# 2021-06-29_LN2_Autofill_Controller.net
KiCad netlist of a schematic drawn in EAGLE
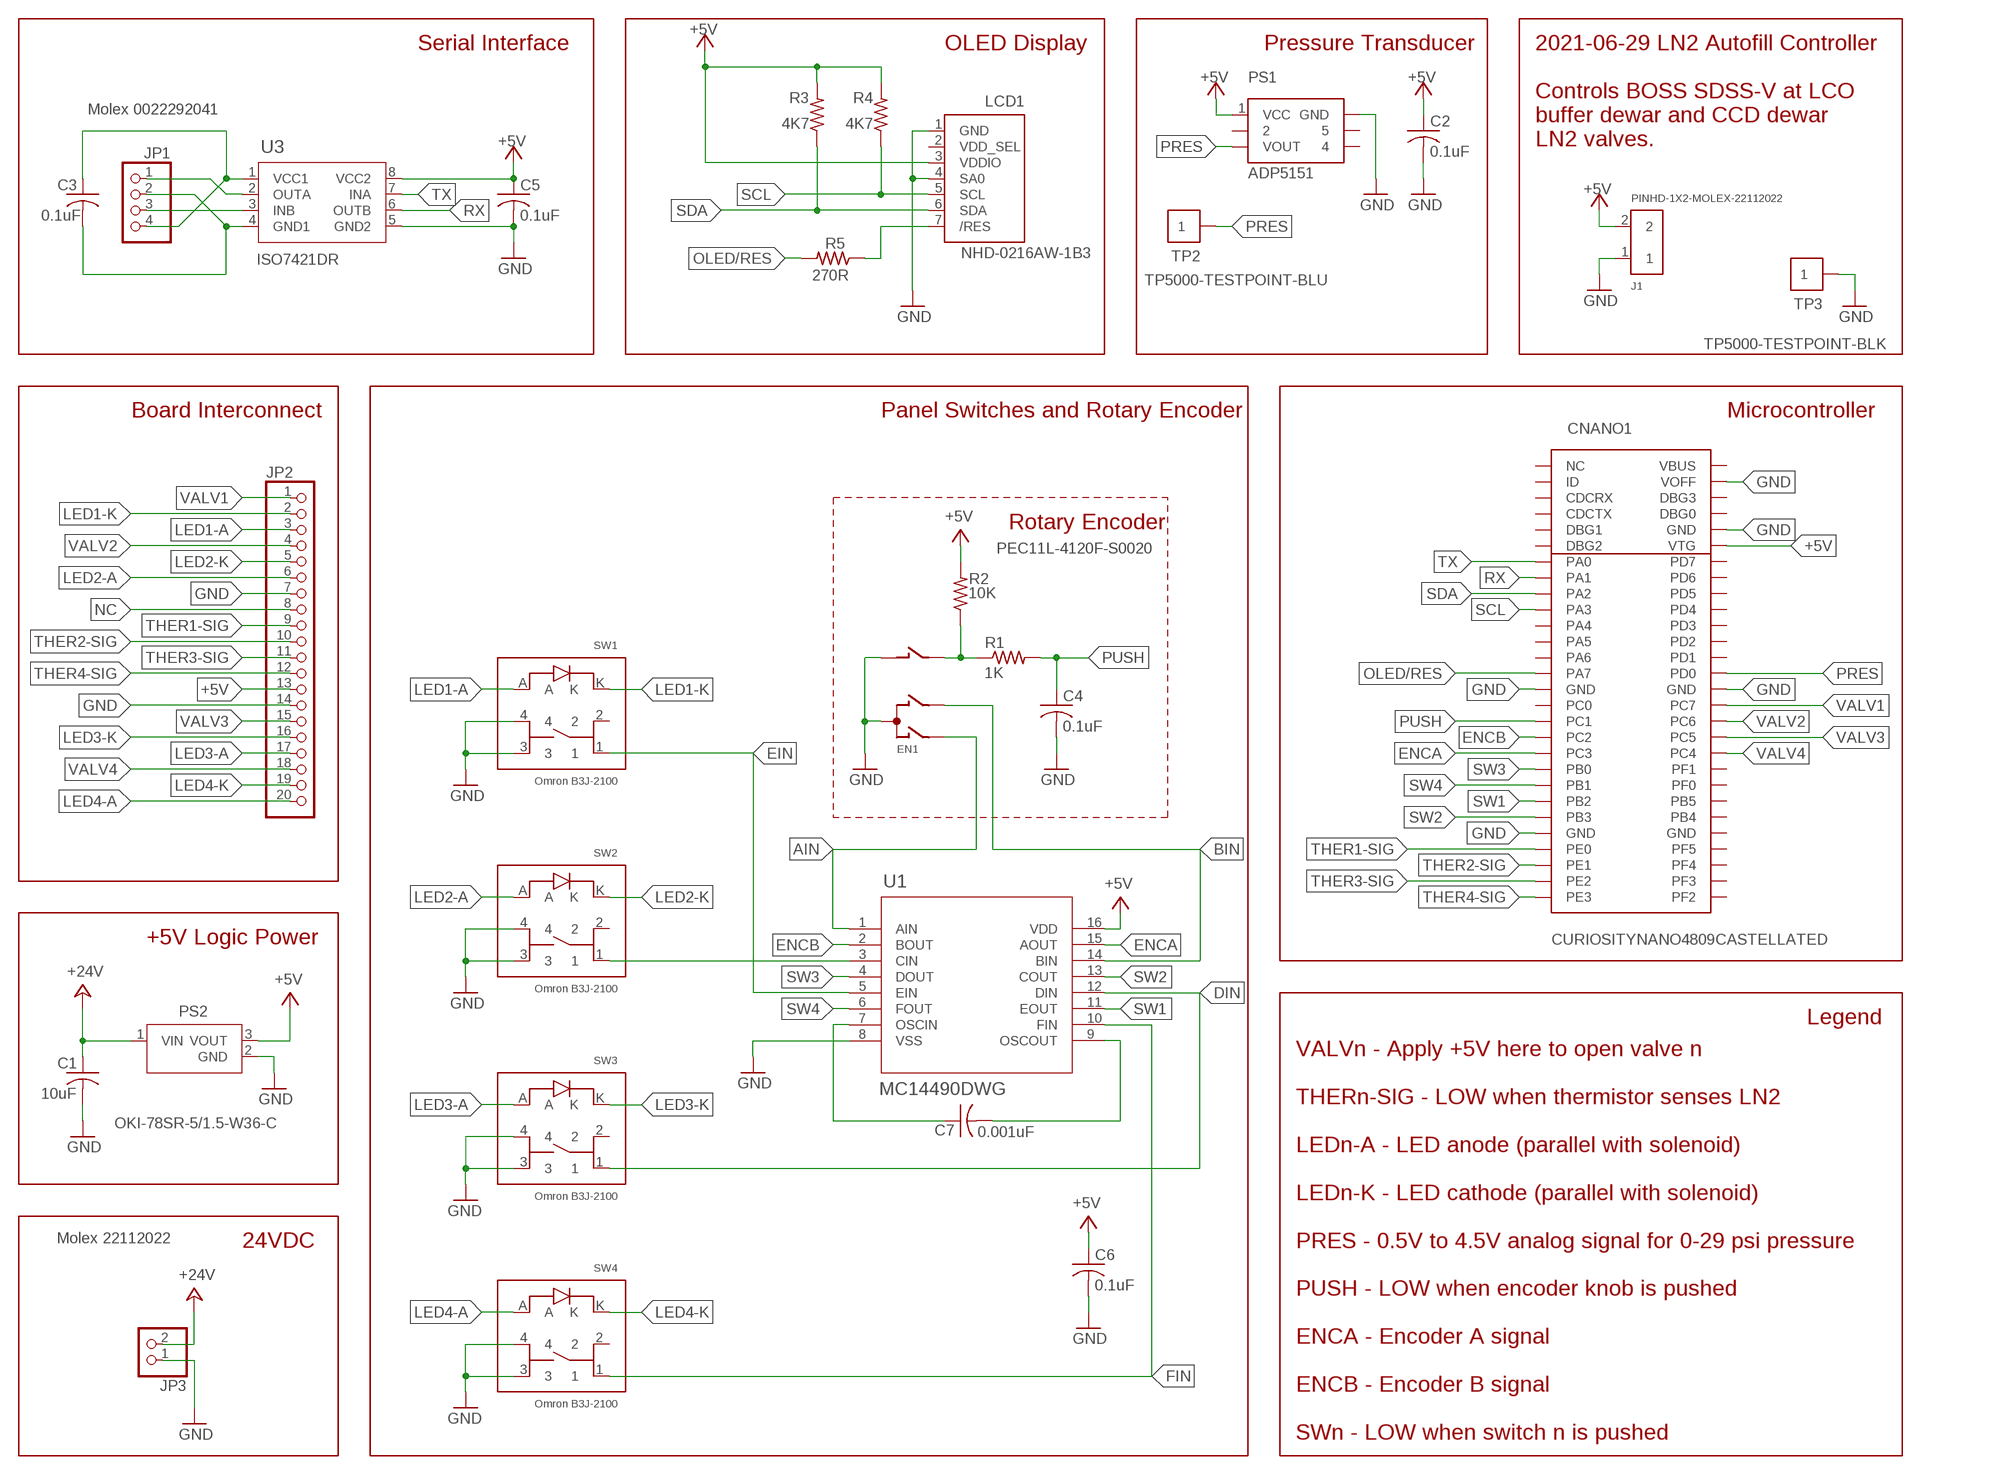
[diagram p0: schematic, sheet 1]

(export (version "E")
  (design (tool "Eeschema 10.0.6"))
  (components
    (comp (ref "C1")
      (value "10uF")
      (footprint "eagle-import:C1210K")
      (libsource (lib "eagle-import") (part "C-USC1210K"))
    )
    (comp (ref "C2")
      (value "0.1uF")
      (footprint "eagle-import:C0805")
      (libsource (lib "eagle-import") (part "C-USC0805"))
    )
    (comp (ref "C3")
      (value "0.1uF")
      (footprint "eagle-import:C0805")
      (libsource (lib "eagle-import") (part "C-USC0805"))
    )
    (comp (ref "C4")
      (value "0.1uF")
      (footprint "eagle-import:C0805")
      (libsource (lib "eagle-import") (part "C-USC0805"))
    )
    (comp (ref "C5")
      (value "0.1uF")
      (footprint "eagle-import:C0805")
      (libsource (lib "eagle-import") (part "C-USC0805"))
    )
    (comp (ref "C6")
      (value "0.1uF")
      (footprint "eagle-import:C0805")
      (libsource (lib "eagle-import") (part "C-USC0805"))
    )
    (comp (ref "C7")
      (value "0.001uF")
      (footprint "eagle-import:C0805")
      (libsource (lib "eagle-import") (part "C-USC0805"))
    )
    (comp (ref "CNANO1")
      (value "CURIOSITYNANO4809CASTELLATED")
      (footprint "eagle-import:CURIOSITYNANO4809CASTELLATED")
      (libsource (lib "eagle-import") (part "CURIOSITYNANO4809CASTELLATED"))
    )
    (comp (ref "EN1")
      (value "PEC11L-4120F-S0020")
      (footprint "eagle-import:ENC-BOURNES-PEC11L")
      (libsource (lib "eagle-import") (part "ENC-BOURNES-PEC11L"))
    )
    (comp (ref "J1")
      (value "PINHD-1X2-MOLEX-22112022")
      (footprint "eagle-import:1X02-MOLEX-22112022")
      (libsource (lib "eagle-import") (part "PINHD-1X2-MOLEX-22112022"))
    )
    (comp (ref "JP1")
      (value "Molex 0022292041")
      (footprint "eagle-import:MOLEX-04-VERT")
      (libsource (lib "eagle-import") (part "PINHD-1X4MOLEX-04-VERT"))
    )
    (comp (ref "JP2")
      (value "PINHD-1X20")
      (footprint "eagle-import:1X20")
      (libsource (lib "eagle-import") (part "PINHD-1X20"))
    )
    (comp (ref "JP3")
      (value "Molex 22112022")
      (footprint "eagle-import:MOLEX-02-VERT")
      (libsource (lib "eagle-import") (part "PINHD-1X2MOLEX-02-VERT"))
    )
    (comp (ref "LCD1")
      (value "NHD-0216AW-1B3")
      (footprint "eagle-import:LCD-NEWHAVEN-16X2")
      (libsource (lib "eagle-import") (part "LCD-NEWHAVEN-16X2"))
    )
    (comp (ref "PS1")
      (value "ADP5151")
      (footprint "eagle-import:PRESSURE-SENSOR-ADP5151")
      (libsource (lib "eagle-import") (part "PRESSURE-SENSOR-ADP5151"))
    )
    (comp (ref "PS2")
      (value "OKI-78SR-5/1.5-W36-C")
      (footprint "eagle-import:CONV_OKI-78SR-5_1.5-W36-C")
      (fields
        (field (name "DIGI-KEY_PART_NUMBER") "811-2196-5-ND")
        (field (name "MF") "Murata Power Solutions Inc.")
      )
      (libsource (lib "eagle-import") (part "OKI-78SR-5/1.5-W36-C"))
    )
    (comp (ref "R1")
      (value "1K")
      (footprint "eagle-import:R0805")
      (libsource (lib "eagle-import") (part "R-US_R0805"))
    )
    (comp (ref "R2")
      (value "10K")
      (footprint "eagle-import:R0805")
      (libsource (lib "eagle-import") (part "R-US_R0805"))
    )
    (comp (ref "R3")
      (value "4K7")
      (footprint "eagle-import:R0805")
      (libsource (lib "eagle-import") (part "R-US_R0805"))
    )
    (comp (ref "R4")
      (value "4K7")
      (footprint "eagle-import:R0805")
      (libsource (lib "eagle-import") (part "R-US_R0805"))
    )
    (comp (ref "R5")
      (value "270R")
      (footprint "eagle-import:R0805")
      (libsource (lib "eagle-import") (part "R-US_R0805"))
    )
    (comp (ref "SW1")
      (value "Omron B3J-2100")
      (footprint "eagle-import:SWITCH-OMRON-B3J-1LED")
      (libsource (lib "eagle-import") (part "SWITCH-OMRON-B3J-1LED"))
    )
    (comp (ref "SW2")
      (value "Omron B3J-2100")
      (footprint "eagle-import:SWITCH-OMRON-B3J-1LED")
      (libsource (lib "eagle-import") (part "SWITCH-OMRON-B3J-1LED"))
    )
    (comp (ref "SW3")
      (value "Omron B3J-2100")
      (footprint "eagle-import:SWITCH-OMRON-B3J-1LED")
      (libsource (lib "eagle-import") (part "SWITCH-OMRON-B3J-1LED"))
    )
    (comp (ref "SW4")
      (value "Omron B3J-2100")
      (footprint "eagle-import:SWITCH-OMRON-B3J-1LED")
      (libsource (lib "eagle-import") (part "SWITCH-OMRON-B3J-1LED"))
    )
    (comp (ref "TP2")
      (value "TP5000-TESTPOINT-BLU")
      (footprint "eagle-import:TP5000-TESTPOINT-BLU")
      (libsource (lib "eagle-import") (part "TP5000-TESTPOINT-BLU"))
    )
    (comp (ref "TP3")
      (value "TP5000-TESTPOINT-BLK")
      (footprint "eagle-import:TP5000-TESTPOINT-BLK")
      (libsource (lib "eagle-import") (part "TP5000-TESTPOINT-BLK"))
    )
    (comp (ref "U1")
      (value "MC14490DWG")
      (footprint "eagle-import:SOIC127P1030X265-16N")
      (libsource (lib "eagle-import") (part "DEBOUNCER-MC14490DWGSOIC-16-WB"))
    )
    (comp (ref "U3")
      (value "ISO7421DR")
      (footprint "eagle-import:SOIC127P599X175-8N")
      (libsource (lib "eagle-import") (part "ISO7421DRTI-SOIC-D8"))
    )
  )
  (nets
    (net (code "1") (name "+5V") (class "Default")
      (node (ref "C2") (pin "1") (pinfunction "1_1") (pintype "passive"))
      (node (ref "C5") (pin "1") (pinfunction "1_1") (pintype "passive"))
      (node (ref "C6") (pin "1") (pinfunction "1_1") (pintype "passive"))
      (node (ref "CNANO1") (pin "VTG") (pinfunction "VTG_VTG") (pintype "bidirectional"))
      (node (ref "J1") (pin "2") (pinfunction "2_2") (pintype "bidirectional"))
      (node (ref "JP2") (pin "13") (pinfunction "13_13") (pintype "passive"))
      (node (ref "LCD1") (pin "3") (pinfunction "VDDIO_3") (pintype "bidirectional"))
      (node (ref "PS1") (pin "1") (pinfunction "VCC_1") (pintype "bidirectional"))
      (node (ref "PS2") (pin "3") (pinfunction "VOUT_3") (pintype "power_in"))
      (node (ref "R2") (pin "2") (pinfunction "2_2") (pintype "passive"))
      (node (ref "R3") (pin "2") (pinfunction "2_2") (pintype "passive"))
      (node (ref "R4") (pin "2") (pinfunction "2_2") (pintype "passive"))
      (node (ref "U1") (pin "16") (pinfunction "VDD_16") (pintype "power_in"))
      (node (ref "U3") (pin "8") (pinfunction "VCC2_8") (pintype "power_in"))
    )
    (net (code "2") (name "+24V") (class "Default")
      (node (ref "C1") (pin "1") (pinfunction "1_1") (pintype "passive"))
      (node (ref "JP3") (pin "2") (pinfunction "2_2") (pintype "passive"))
      (node (ref "PS2") (pin "1") (pinfunction "VIN_1") (pintype "input"))
    )
    (net (code "3") (name "AIN") (class "Default")
      (node (ref "EN1") (pin "A") (pinfunction "A_A") (pintype "passive"))
      (node (ref "U1") (pin "1") (pinfunction "AIN_1") (pintype "input"))
    )
    (net (code "4") (name "BIN") (class "Default")
      (node (ref "EN1") (pin "B") (pinfunction "B_B") (pintype "passive"))
      (node (ref "U1") (pin "14") (pinfunction "BIN_14") (pintype "input"))
    )
    (net (code "5") (name "DIN") (class "Default")
      (node (ref "SW3") (pin "1") (pinfunction "1_1") (pintype "bidirectional"))
      (node (ref "U1") (pin "12") (pinfunction "DIN_12") (pintype "input"))
    )
    (net (code "6") (name "EIN") (class "Default")
      (node (ref "SW1") (pin "1") (pinfunction "1_1") (pintype "bidirectional"))
      (node (ref "U1") (pin "5") (pinfunction "EIN_5") (pintype "input"))
    )
    (net (code "7") (name "ENCA") (class "Default")
      (node (ref "CNANO1") (pin "PC3") (pinfunction "PC3_PC3") (pintype "bidirectional"))
      (node (ref "U1") (pin "15") (pinfunction "AOUT_15") (pintype "output"))
    )
    (net (code "8") (name "ENCB") (class "Default")
      (node (ref "CNANO1") (pin "PC2") (pinfunction "PC2_PC2") (pintype "bidirectional"))
      (node (ref "U1") (pin "2") (pinfunction "BOUT_2") (pintype "output"))
    )
    (net (code "9") (name "FIN") (class "Default")
      (node (ref "SW4") (pin "1") (pinfunction "1_1") (pintype "bidirectional"))
      (node (ref "U1") (pin "10") (pinfunction "FIN_10") (pintype "input"))
    )
    (net (code "10") (name "GND") (class "Default")
      (node (ref "C1") (pin "2") (pinfunction "2_2") (pintype "passive"))
      (node (ref "C2") (pin "2") (pinfunction "2_2") (pintype "passive"))
      (node (ref "C4") (pin "2") (pinfunction "2_2") (pintype "passive"))
      (node (ref "C5") (pin "2") (pinfunction "2_2") (pintype "passive"))
      (node (ref "C6") (pin "2") (pinfunction "2_2") (pintype "passive"))
      (node (ref "CNANO1") (pin "GND15") (pinfunction "GND_GND15") (pintype "bidirectional"))
      (node (ref "CNANO1") (pin "GND24") (pinfunction "GND_GND24") (pintype "bidirectional"))
      (node (ref "CNANO1") (pin "GND42") (pinfunction "GND_GND42") (pintype "bidirectional"))
      (node (ref "CNANO1") (pin "GND52") (pinfunction "GND_GND52") (pintype "bidirectional"))
      (node (ref "CNANO1") (pin "VOFF") (pinfunction "VOFF_VOFF") (pintype "bidirectional"))
      (node (ref "EN1") (pin "2") (pinfunction "C1_2") (pintype "passive"))
      (node (ref "EN1") (pin "C") (pinfunction "C_C") (pintype "passive"))
      (node (ref "J1") (pin "1") (pinfunction "1_1") (pintype "bidirectional"))
      (node (ref "JP2") (pin "14") (pinfunction "14_14") (pintype "passive"))
      (node (ref "JP2") (pin "7") (pinfunction "7_7") (pintype "passive"))
      (node (ref "JP3") (pin "1") (pinfunction "1_1") (pintype "passive"))
      (node (ref "LCD1") (pin "1") (pinfunction "GND_1") (pintype "bidirectional"))
      (node (ref "LCD1") (pin "4") (pinfunction "SA0_4") (pintype "bidirectional"))
      (node (ref "PS1") (pin "6") (pinfunction "GND_6") (pintype "bidirectional"))
      (node (ref "PS2") (pin "2") (pinfunction "GND_2") (pintype "power_in"))
      (node (ref "SW1") (pin "3") (pinfunction "3_3") (pintype "bidirectional"))
      (node (ref "SW1") (pin "4") (pinfunction "4_4") (pintype "bidirectional"))
      (node (ref "SW2") (pin "3") (pinfunction "3_3") (pintype "bidirectional"))
      (node (ref "SW2") (pin "4") (pinfunction "4_4") (pintype "bidirectional"))
      (node (ref "SW3") (pin "3") (pinfunction "3_3") (pintype "bidirectional"))
      (node (ref "SW3") (pin "4") (pinfunction "4_4") (pintype "bidirectional"))
      (node (ref "SW4") (pin "3") (pinfunction "3_3") (pintype "bidirectional"))
      (node (ref "SW4") (pin "4") (pinfunction "4_4") (pintype "bidirectional"))
      (node (ref "TP3") (pin "P$1") (pinfunction "1_P$1") (pintype "bidirectional"))
      (node (ref "U1") (pin "8") (pinfunction "VSS_8") (pintype "power_in"))
      (node (ref "U3") (pin "5") (pinfunction "GND2_5") (pintype "power_in"))
    )
    (net (code "11") (name "LED1-A") (class "Default")
      (node (ref "JP2") (pin "3") (pinfunction "3_3") (pintype "passive"))
      (node (ref "SW1") (pin "A") (pinfunction "A_A") (pintype "bidirectional"))
    )
    (net (code "12") (name "LED1-K") (class "Default")
      (node (ref "JP2") (pin "2") (pinfunction "2_2") (pintype "passive"))
      (node (ref "SW1") (pin "K") (pinfunction "K_K") (pintype "bidirectional"))
    )
    (net (code "13") (name "LED2-A") (class "Default")
      (node (ref "JP2") (pin "6") (pinfunction "6_6") (pintype "passive"))
      (node (ref "SW2") (pin "A") (pinfunction "A_A") (pintype "bidirectional"))
    )
    (net (code "14") (name "LED2-K") (class "Default")
      (node (ref "JP2") (pin "5") (pinfunction "5_5") (pintype "passive"))
      (node (ref "SW2") (pin "K") (pinfunction "K_K") (pintype "bidirectional"))
    )
    (net (code "15") (name "LED3-A") (class "Default")
      (node (ref "JP2") (pin "17") (pinfunction "17_17") (pintype "passive"))
      (node (ref "SW3") (pin "A") (pinfunction "A_A") (pintype "bidirectional"))
    )
    (net (code "16") (name "LED3-K") (class "Default")
      (node (ref "JP2") (pin "16") (pinfunction "16_16") (pintype "passive"))
      (node (ref "SW3") (pin "K") (pinfunction "K_K") (pintype "bidirectional"))
    )
    (net (code "17") (name "LED4-A") (class "Default")
      (node (ref "JP2") (pin "20") (pinfunction "20_20") (pintype "passive"))
      (node (ref "SW4") (pin "A") (pinfunction "A_A") (pintype "bidirectional"))
    )
    (net (code "18") (name "LED4-K") (class "Default")
      (node (ref "JP2") (pin "19") (pinfunction "19_19") (pintype "passive"))
      (node (ref "SW4") (pin "K") (pinfunction "K_K") (pintype "bidirectional"))
    )
    (net (code "19") (name "NC") (class "Default")
      (node (ref "JP2") (pin "8") (pinfunction "8_8") (pintype "passive"))
    )
    (net (code "20") (name "Net-(EN1-B1)") (class "Default")
      (node (ref "EN1") (pin "1") (pinfunction "B1_1") (pintype "passive"))
      (node (ref "R1") (pin "1") (pinfunction "1_1") (pintype "passive"))
      (node (ref "R2") (pin "1") (pinfunction "1_1") (pintype "passive"))
    )
    (net (code "21") (name "Net-(LCD1-{slash}RES)") (class "Default")
      (node (ref "LCD1") (pin "7") (pinfunction "/RES_7") (pintype "bidirectional"))
      (node (ref "R5") (pin "1") (pinfunction "1_1") (pintype "passive"))
    )
    (net (code "22") (name "Net-(U1-CIN)") (class "Default")
      (node (ref "SW2") (pin "1") (pinfunction "1_1") (pintype "bidirectional"))
      (node (ref "U1") (pin "3") (pinfunction "CIN_3") (pintype "input"))
    )
    (net (code "23") (name "Net-(U1-OSCIN)") (class "Default")
      (node (ref "C7") (pin "1") (pinfunction "1_1") (pintype "passive"))
      (node (ref "U1") (pin "7") (pinfunction "OSCIN_7") (pintype "input"))
    )
    (net (code "24") (name "Net-(U1-OSCOUT)") (class "Default")
      (node (ref "C7") (pin "2") (pinfunction "2_2") (pintype "passive"))
      (node (ref "U1") (pin "9") (pinfunction "OSCOUT_9") (pintype "output"))
    )
    (net (code "25") (name "Net-(U3-GND1)") (class "Default")
      (node (ref "C3") (pin "2") (pinfunction "2_2") (pintype "passive"))
      (node (ref "JP1") (pin "2") (pinfunction "2_2") (pintype "passive"))
      (node (ref "U3") (pin "4") (pinfunction "GND1_4") (pintype "power_in"))
    )
    (net (code "26") (name "Net-(U3-INB)") (class "Default")
      (node (ref "JP1") (pin "3") (pinfunction "3_3") (pintype "passive"))
      (node (ref "U3") (pin "3") (pinfunction "INB_3") (pintype "input"))
    )
    (net (code "27") (name "Net-(U3-OUTA)") (class "Default")
      (node (ref "JP1") (pin "1") (pinfunction "1_1") (pintype "passive"))
      (node (ref "U3") (pin "2") (pinfunction "OUTA_2") (pintype "output"))
    )
    (net (code "28") (name "Net-(U3-VCC1)") (class "Default")
      (node (ref "C3") (pin "1") (pinfunction "1_1") (pintype "passive"))
      (node (ref "JP1") (pin "4") (pinfunction "4_4") (pintype "passive"))
      (node (ref "U3") (pin "1") (pinfunction "VCC1_1") (pintype "power_in"))
    )
    (net (code "29") (name "OLED{slash}RES") (class "Default")
      (node (ref "CNANO1") (pin "PA7-SS") (pinfunction "PA7_PA7-SS") (pintype "bidirectional"))
      (node (ref "R5") (pin "2") (pinfunction "2_2") (pintype "passive"))
    )
    (net (code "30") (name "PRES") (class "Default")
      (node (ref "CNANO1") (pin "PD0-AIN0") (pinfunction "PD0_PD0-AIN0") (pintype "bidirectional"))
      (node (ref "PS1") (pin "3") (pinfunction "VOUT_3") (pintype "bidirectional"))
      (node (ref "TP2") (pin "P$1") (pinfunction "1_P$1") (pintype "bidirectional"))
    )
    (net (code "31") (name "PUSH") (class "Default")
      (node (ref "C4") (pin "1") (pinfunction "1_1") (pintype "passive"))
      (node (ref "CNANO1") (pin "PC1-RX") (pinfunction "PC1_PC1-RX") (pintype "bidirectional"))
      (node (ref "R1") (pin "2") (pinfunction "2_2") (pintype "passive"))
    )
    (net (code "32") (name "RX") (class "Default")
      (node (ref "CNANO1") (pin "PA1-RX") (pinfunction "PA1_PA1-RX") (pintype "bidirectional"))
      (node (ref "U3") (pin "6") (pinfunction "OUTB_6") (pintype "output"))
    )
    (net (code "33") (name "SCL") (class "Default")
      (node (ref "CNANO1") (pin "PA3-SCL") (pinfunction "PA3_PA3-SCL") (pintype "bidirectional"))
      (node (ref "LCD1") (pin "5") (pinfunction "SCL_5") (pintype "bidirectional"))
      (node (ref "R4") (pin "1") (pinfunction "1_1") (pintype "passive"))
    )
    (net (code "34") (name "SDA") (class "Default")
      (node (ref "CNANO1") (pin "PA2-SDA") (pinfunction "PA2_PA2-SDA") (pintype "bidirectional"))
      (node (ref "LCD1") (pin "6") (pinfunction "SDA_6") (pintype "bidirectional"))
      (node (ref "R3") (pin "1") (pinfunction "1_1") (pintype "passive"))
    )
    (net (code "35") (name "SW1") (class "Default")
      (node (ref "CNANO1") (pin "PB2") (pinfunction "PB2_PB2") (pintype "bidirectional"))
      (node (ref "U1") (pin "11") (pinfunction "EOUT_11") (pintype "output"))
    )
    (net (code "36") (name "SW2") (class "Default")
      (node (ref "CNANO1") (pin "PB3") (pinfunction "PB3_PB3") (pintype "bidirectional"))
      (node (ref "U1") (pin "13") (pinfunction "COUT_13") (pintype "output"))
    )
    (net (code "37") (name "SW3") (class "Default")
      (node (ref "CNANO1") (pin "PB0-TX") (pinfunction "PB0_PB0-TX") (pintype "bidirectional"))
      (node (ref "U1") (pin "4") (pinfunction "DOUT_4") (pintype "output"))
    )
    (net (code "38") (name "SW4") (class "Default")
      (node (ref "CNANO1") (pin "PB1-RX") (pinfunction "PB1_PB1-RX") (pintype "bidirectional"))
      (node (ref "U1") (pin "6") (pinfunction "FOUT_6") (pintype "output"))
    )
    (net (code "39") (name "THER1-SIG") (class "Default")
      (node (ref "CNANO1") (pin "PE0") (pinfunction "PE0_PE0") (pintype "bidirectional"))
      (node (ref "JP2") (pin "9") (pinfunction "9_9") (pintype "passive"))
    )
    (net (code "40") (name "THER2-SIG") (class "Default")
      (node (ref "CNANO1") (pin "PE1") (pinfunction "PE1_PE1") (pintype "bidirectional"))
      (node (ref "JP2") (pin "10") (pinfunction "10_10") (pintype "passive"))
    )
    (net (code "41") (name "THER3-SIG") (class "Default")
      (node (ref "CNANO1") (pin "PE2") (pinfunction "PE2_PE2") (pintype "bidirectional"))
      (node (ref "JP2") (pin "11") (pinfunction "11_11") (pintype "passive"))
    )
    (net (code "42") (name "THER4-SIG") (class "Default")
      (node (ref "CNANO1") (pin "PE3") (pinfunction "PE3_PE3") (pintype "bidirectional"))
      (node (ref "JP2") (pin "12") (pinfunction "12_12") (pintype "passive"))
    )
    (net (code "43") (name "TX") (class "Default")
      (node (ref "CNANO1") (pin "PA0-TX") (pinfunction "PA0_PA0-TX") (pintype "bidirectional"))
      (node (ref "U3") (pin "7") (pinfunction "INA_7") (pintype "input"))
    )
    (net (code "44") (name "VALV1") (class "Default")
      (node (ref "CNANO1") (pin "PC7") (pinfunction "PC7_PC7") (pintype "bidirectional"))
      (node (ref "JP2") (pin "1") (pinfunction "1_1") (pintype "passive"))
    )
    (net (code "45") (name "VALV2") (class "Default")
      (node (ref "CNANO1") (pin "PC6") (pinfunction "PC6_PC6") (pintype "bidirectional"))
      (node (ref "JP2") (pin "4") (pinfunction "4_4") (pintype "passive"))
    )
    (net (code "46") (name "VALV3") (class "Default")
      (node (ref "CNANO1") (pin "PC5") (pinfunction "PC5_PC5") (pintype "bidirectional"))
      (node (ref "JP2") (pin "15") (pinfunction "15_15") (pintype "passive"))
    )
    (net (code "47") (name "VALV4") (class "Default")
      (node (ref "CNANO1") (pin "PC4") (pinfunction "PC4_PC4") (pintype "bidirectional"))
      (node (ref "JP2") (pin "18") (pinfunction "18_18") (pintype "passive"))
    )
    (net (code "48") (name "unconnected-(CNANO1-CDCRX-PadPB0-RX)") (class "Default")
      (node (ref "CNANO1") (pin "PB0-RX") (pinfunction "CDCRX_PB0-RX") (pintype "bidirectional"))
    )
    (net (code "49") (name "unconnected-(CNANO1-CDCTX-PadPB1-TX)") (class "Default")
      (node (ref "CNANO1") (pin "PB1-TX") (pinfunction "CDCTX_PB1-TX") (pintype "bidirectional"))
    )
    (net (code "50") (name "unconnected-(CNANO1-DBG0-PadUPDI)") (class "Default")
      (node (ref "CNANO1") (pin "UPDI") (pinfunction "DBG0_UPDI") (pintype "bidirectional"))
    )
    (net (code "51") (name "unconnected-(CNANO1-DBG1-PadPF3-5)") (class "Default")
      (node (ref "CNANO1") (pin "PF3-5") (pinfunction "DBG1_PF3-5") (pintype "bidirectional"))
    )
    (net (code "52") (name "unconnected-(CNANO1-DBG2-PadPF2-6)") (class "Default")
      (node (ref "CNANO1") (pin "PF2-6") (pinfunction "DBG2_PF2-6") (pintype "bidirectional"))
    )
    (net (code "53") (name "unconnected-(CNANO1-DBG3-PadPF6-SW0)") (class "Default")
      (node (ref "CNANO1") (pin "PF6-SW0") (pinfunction "DBG3_PF6-SW0") (pintype "bidirectional"))
    )
    (net (code "54") (name "unconnected-(CNANO1-GND-PadGND33)") (class "Default")
      (node (ref "CNANO1") (pin "GND33") (pinfunction "GND_GND33") (pintype "bidirectional"))
    )
    (net (code "55") (name "unconnected-(CNANO1-PA4-PadPA4-MOSI)") (class "Default")
      (node (ref "CNANO1") (pin "PA4-MOSI") (pinfunction "PA4_PA4-MOSI") (pintype "bidirectional"))
    )
    (net (code "56") (name "unconnected-(CNANO1-PA5-PadPA5-MISO)") (class "Default")
      (node (ref "CNANO1") (pin "PA5-MISO") (pinfunction "PA5_PA5-MISO") (pintype "bidirectional"))
    )
    (net (code "57") (name "unconnected-(CNANO1-PA6-PadPA6-SCK)") (class "Default")
      (node (ref "CNANO1") (pin "PA6-SCK") (pinfunction "PA6_PA6-SCK") (pintype "bidirectional"))
    )
    (net (code "58") (name "unconnected-(CNANO1-PC0-PadPC0-TX)") (class "Default")
      (node (ref "CNANO1") (pin "PC0-TX") (pinfunction "PC0_PC0-TX") (pintype "bidirectional"))
    )
    (net (code "59") (name "unconnected-(CNANO1-PD1-PadPD1-AIN1)") (class "Default")
      (node (ref "CNANO1") (pin "PD1-AIN1") (pinfunction "PD1_PD1-AIN1") (pintype "bidirectional"))
    )
    (net (code "60") (name "unconnected-(CNANO1-PD2-PadPD2-AIN2)") (class "Default")
      (node (ref "CNANO1") (pin "PD2-AIN2") (pinfunction "PD2_PD2-AIN2") (pintype "bidirectional"))
    )
    (net (code "61") (name "unconnected-(CNANO1-PD3-PadPD3-AIN3)") (class "Default")
      (node (ref "CNANO1") (pin "PD3-AIN3") (pinfunction "PD3_PD3-AIN3") (pintype "bidirectional"))
    )
    (net (code "62") (name "unconnected-(CNANO1-PD4-PadPD4-AIN4)") (class "Default")
      (node (ref "CNANO1") (pin "PD4-AIN4") (pinfunction "PD4_PD4-AIN4") (pintype "bidirectional"))
    )
    (net (code "63") (name "unconnected-(CNANO1-PD5-PadPD5-AIN5)") (class "Default")
      (node (ref "CNANO1") (pin "PD5-AIN5") (pinfunction "PD5_PD5-AIN5") (pintype "bidirectional"))
    )
    (net (code "64") (name "unconnected-(CNANO1-PD6-PadPD6-AIN6)") (class "Default")
      (node (ref "CNANO1") (pin "PD6-AIN6") (pinfunction "PD6_PD6-AIN6") (pintype "bidirectional"))
    )
    (net (code "65") (name "unconnected-(CNANO1-PD7-PadPD7-AIN7)") (class "Default")
      (node (ref "CNANO1") (pin "PD7-AIN7") (pinfunction "PD7_PD7-AIN7") (pintype "bidirectional"))
    )
    (net (code "66") (name "unconnected-(CNANO1-PF0-PadPF0-TOSC1)") (class "Default")
      (node (ref "CNANO1") (pin "PF0-TOSC1") (pinfunction "PF0_PF0-TOSC1") (pintype "bidirectional"))
    )
    (net (code "67") (name "unconnected-(CNANO1-PF1-PadPF1-TOSC2)") (class "Default")
      (node (ref "CNANO1") (pin "PF1-TOSC2") (pinfunction "PF1_PF1-TOSC2") (pintype "bidirectional"))
    )
    (net (code "68") (name "unconnected-(CNANO1-PF5-PadPF5-LED)") (class "Default")
      (node (ref "CNANO1") (pin "PF5-LED") (pinfunction "PF5_PF5-LED") (pintype "bidirectional"))
    )
    (net (code "69") (name "unconnected-(CNANO1-PadID)") (class "Default")
      (node (ref "CNANO1") (pin "ID") (pinfunction "ID_ID") (pintype "bidirectional"))
    )
    (net (code "70") (name "unconnected-(CNANO1-PadNC)") (class "Default")
      (node (ref "CNANO1") (pin "NC") (pinfunction "NC_NC") (pintype "bidirectional"))
    )
    (net (code "71") (name "unconnected-(CNANO1-PadPB4)") (class "Default")
      (node (ref "CNANO1") (pin "PB4") (pinfunction "PB4_PB4") (pintype "bidirectional"))
    )
    (net (code "72") (name "unconnected-(CNANO1-PadPB5)") (class "Default")
      (node (ref "CNANO1") (pin "PB5") (pinfunction "PB5_PB5") (pintype "bidirectional"))
    )
    (net (code "73") (name "unconnected-(CNANO1-PadPF2)") (class "Default")
      (node (ref "CNANO1") (pin "PF2") (pinfunction "PF2_PF2") (pintype "bidirectional"))
    )
    (net (code "74") (name "unconnected-(CNANO1-PadPF3)") (class "Default")
      (node (ref "CNANO1") (pin "PF3") (pinfunction "PF3_PF3") (pintype "bidirectional"))
    )
    (net (code "75") (name "unconnected-(CNANO1-PadPF4)") (class "Default")
      (node (ref "CNANO1") (pin "PF4") (pinfunction "PF4_PF4") (pintype "bidirectional"))
    )
    (net (code "76") (name "unconnected-(CNANO1-PadVBUS)") (class "Default")
      (node (ref "CNANO1") (pin "VBUS") (pinfunction "VBUS_VBUS") (pintype "bidirectional"))
    )
    (net (code "77") (name "unconnected-(LCD1-VDD_SEL-Pad2)") (class "Default")
      (node (ref "LCD1") (pin "2") (pinfunction "VDD_SEL_2") (pintype "bidirectional"))
    )
    (net (code "78") (name "unconnected-(PS1-Pad2)") (class "Default")
      (node (ref "PS1") (pin "2") (pinfunction "2_2") (pintype "bidirectional"))
    )
    (net (code "79") (name "unconnected-(PS1-Pad4)") (class "Default")
      (node (ref "PS1") (pin "4") (pinfunction "4_4") (pintype "bidirectional"))
    )
    (net (code "80") (name "unconnected-(PS1-Pad5)") (class "Default")
      (node (ref "PS1") (pin "5") (pinfunction "5_5") (pintype "bidirectional"))
    )
    (net (code "81") (name "unconnected-(SW1-Pad2)") (class "Default")
      (node (ref "SW1") (pin "2") (pinfunction "2_2") (pintype "bidirectional"))
    )
    (net (code "82") (name "unconnected-(SW2-Pad2)") (class "Default")
      (node (ref "SW2") (pin "2") (pinfunction "2_2") (pintype "bidirectional"))
    )
    (net (code "83") (name "unconnected-(SW3-Pad2)") (class "Default")
      (node (ref "SW3") (pin "2") (pinfunction "2_2") (pintype "bidirectional"))
    )
    (net (code "84") (name "unconnected-(SW4-Pad2)") (class "Default")
      (node (ref "SW4") (pin "2") (pinfunction "2_2") (pintype "bidirectional"))
    )
  )
)
